# ai_orb-8.net
KiCad netlist of a schematic drawn in EAGLE
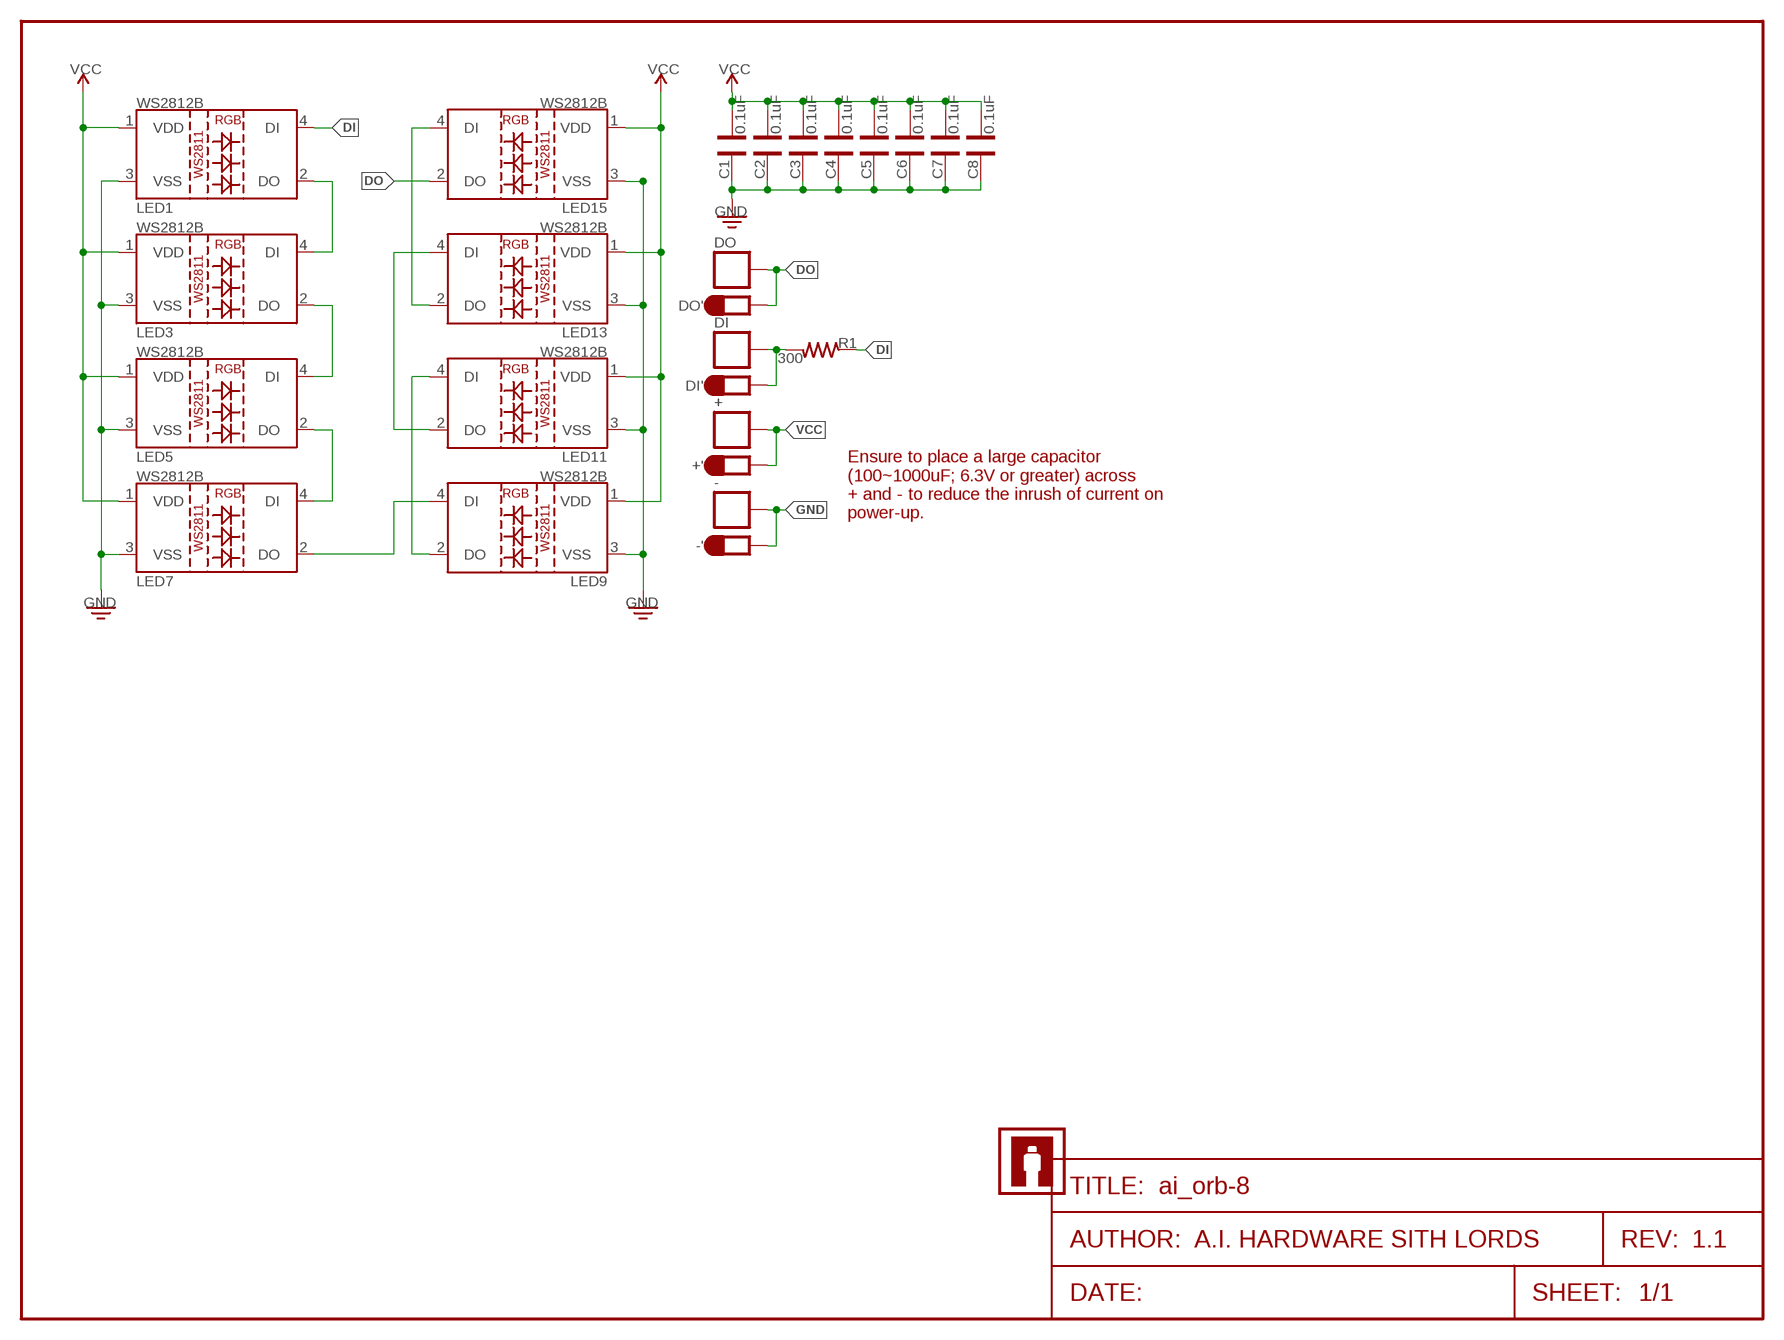
[diagram p0: schematic, sheet 1]

(export (version "E")
  (design (tool "Eeschema 10.0.6"))
  (components
    (comp (ref "+")
      (value "1X01-SM")
      (footprint "eagle-import:1X01-SM")
      (libsource (lib "eagle-import") (part "1X01-SM"))
    )
    (comp (ref "+'")
      (value "1X01-PETAL")
      (footprint "eagle-import:1X01-PETAL")
      (libsource (lib "eagle-import") (part "1X01-PETAL"))
    )
    (comp (ref "-")
      (value "1X01-SM")
      (footprint "eagle-import:1X01-SM")
      (libsource (lib "eagle-import") (part "1X01-SM"))
    )
    (comp (ref "-'")
      (value "1X01-PETAL")
      (footprint "eagle-import:1X01-PETAL")
      (libsource (lib "eagle-import") (part "1X01-PETAL"))
    )
    (comp (ref "C1")
      (value "0.1uF")
      (footprint "eagle-import:CAP-0402")
      (libsource (lib "eagle-import") (part "CAP0402"))
    )
    (comp (ref "C2")
      (value "0.1uF")
      (footprint "eagle-import:CAP-0402")
      (libsource (lib "eagle-import") (part "CAP0402"))
    )
    (comp (ref "C3")
      (value "0.1uF")
      (footprint "eagle-import:CAP-0402")
      (libsource (lib "eagle-import") (part "CAP0402"))
    )
    (comp (ref "C4")
      (value "0.1uF")
      (footprint "eagle-import:CAP-0402")
      (libsource (lib "eagle-import") (part "CAP0402"))
    )
    (comp (ref "C5")
      (value "0.1uF")
      (footprint "eagle-import:CAP-0402")
      (libsource (lib "eagle-import") (part "CAP0402"))
    )
    (comp (ref "C6")
      (value "0.1uF")
      (footprint "eagle-import:CAP-0402")
      (libsource (lib "eagle-import") (part "CAP0402"))
    )
    (comp (ref "C7")
      (value "0.1uF")
      (footprint "eagle-import:CAP-0402")
      (libsource (lib "eagle-import") (part "CAP0402"))
    )
    (comp (ref "C8")
      (value "0.1uF")
      (footprint "eagle-import:CAP-0402")
      (libsource (lib "eagle-import") (part "CAP0402"))
    )
    (comp (ref "DI")
      (value "1X01-SM")
      (footprint "eagle-import:1X01-SM")
      (libsource (lib "eagle-import") (part "1X01-SM"))
    )
    (comp (ref "DI'")
      (value "1X01-PETAL")
      (footprint "eagle-import:1X01-PETAL")
      (libsource (lib "eagle-import") (part "1X01-PETAL"))
    )
    (comp (ref "DO")
      (value "1X01-SM")
      (footprint "eagle-import:1X01-SM")
      (libsource (lib "eagle-import") (part "1X01-SM"))
    )
    (comp (ref "DO'")
      (value "1X01-PETAL")
      (footprint "eagle-import:1X01-PETAL")
      (libsource (lib "eagle-import") (part "1X01-PETAL"))
    )
    (comp (ref "LED1")
      (value "LED-WS2812B-SM")
      (footprint "eagle-import:LED-WS2812B-SM")
      (libsource (lib "eagle-import") (part "LED-WS2812B-SM"))
    )
    (comp (ref "LED3")
      (value "LED-WS2812B-SM")
      (footprint "eagle-import:LED-WS2812B-SM")
      (libsource (lib "eagle-import") (part "LED-WS2812B-SM"))
    )
    (comp (ref "LED5")
      (value "LED-WS2812B-SM")
      (footprint "eagle-import:LED-WS2812B-SM")
      (libsource (lib "eagle-import") (part "LED-WS2812B-SM"))
    )
    (comp (ref "LED7")
      (value "LED-WS2812B-SM")
      (footprint "eagle-import:LED-WS2812B-SM")
      (libsource (lib "eagle-import") (part "LED-WS2812B-SM"))
    )
    (comp (ref "LED9")
      (value "LED-WS2812B-SM")
      (footprint "eagle-import:LED-WS2812B-SM")
      (libsource (lib "eagle-import") (part "LED-WS2812B-SM"))
    )
    (comp (ref "LED11")
      (value "LED-WS2812B-SM")
      (footprint "eagle-import:LED-WS2812B-SM")
      (libsource (lib "eagle-import") (part "LED-WS2812B-SM"))
    )
    (comp (ref "LED13")
      (value "LED-WS2812B-SM")
      (footprint "eagle-import:LED-WS2812B-SM")
      (libsource (lib "eagle-import") (part "LED-WS2812B-SM"))
    )
    (comp (ref "LED15")
      (value "LED-WS2812B-SM")
      (footprint "eagle-import:LED-WS2812B-SM")
      (libsource (lib "eagle-import") (part "LED-WS2812B-SM"))
    )
    (comp (ref "LOGO")
      (value "AI-LOGOXS")
      (footprint "eagle-import:AI-LOGO-XS")
      (libsource (lib "eagle-import") (part "AI-LOGOXS"))
    )
    (comp (ref "LOGO1")
      (value "AI-LOGOXS")
      (footprint "eagle-import:AI-LOGO-XS")
      (libsource (lib "eagle-import") (part "AI-LOGOXS"))
    )
    (comp (ref "R1")
      (value "300")
      (footprint "eagle-import:RES-0402")
      (libsource (lib "eagle-import") (part "RES0402"))
    )
  )
  (nets
    (net (code "1") (name "DI") (class "Default")
      (node (ref "LED1") (pin "4") (pinfunction "DI_4") (pintype "bidirectional"))
      (node (ref "R1") (pin "1") (pinfunction "1_1") (pintype "passive"))
    )
    (net (code "2") (name "DO") (class "Default")
      (node (ref "DO") (pin "1") (pinfunction "1_1") (pintype "bidirectional"))
      (node (ref "DO'") (pin "1") (pinfunction "1_1") (pintype "bidirectional"))
      (node (ref "LED15") (pin "2") (pinfunction "DO_2") (pintype "bidirectional"))
    )
    (net (code "3") (name "GND") (class "Default")
      (node (ref "-") (pin "1") (pinfunction "1_1") (pintype "bidirectional"))
      (node (ref "-'") (pin "1") (pinfunction "1_1") (pintype "bidirectional"))
      (node (ref "C1") (pin "2") (pinfunction "2_2") (pintype "passive"))
      (node (ref "C2") (pin "2") (pinfunction "2_2") (pintype "passive"))
      (node (ref "C3") (pin "2") (pinfunction "2_2") (pintype "passive"))
      (node (ref "C4") (pin "2") (pinfunction "2_2") (pintype "passive"))
      (node (ref "C5") (pin "2") (pinfunction "2_2") (pintype "passive"))
      (node (ref "C6") (pin "2") (pinfunction "2_2") (pintype "passive"))
      (node (ref "C7") (pin "2") (pinfunction "2_2") (pintype "passive"))
      (node (ref "C8") (pin "2") (pinfunction "2_2") (pintype "passive"))
      (node (ref "LED1") (pin "3") (pinfunction "VSS_3") (pintype "bidirectional"))
      (node (ref "LED11") (pin "3") (pinfunction "VSS_3") (pintype "bidirectional"))
      (node (ref "LED13") (pin "3") (pinfunction "VSS_3") (pintype "bidirectional"))
      (node (ref "LED15") (pin "3") (pinfunction "VSS_3") (pintype "bidirectional"))
      (node (ref "LED3") (pin "3") (pinfunction "VSS_3") (pintype "bidirectional"))
      (node (ref "LED5") (pin "3") (pinfunction "VSS_3") (pintype "bidirectional"))
      (node (ref "LED7") (pin "3") (pinfunction "VSS_3") (pintype "bidirectional"))
      (node (ref "LED9") (pin "3") (pinfunction "VSS_3") (pintype "bidirectional"))
    )
    (net (code "4") (name "Net-(DI'-Pad1)") (class "Default")
      (node (ref "DI") (pin "1") (pinfunction "1_1") (pintype "bidirectional"))
      (node (ref "DI'") (pin "1") (pinfunction "1_1") (pintype "bidirectional"))
      (node (ref "R1") (pin "2") (pinfunction "2_2") (pintype "passive"))
    )
    (net (code "5") (name "Net-(LED1-DO)") (class "Default")
      (node (ref "LED1") (pin "2") (pinfunction "DO_2") (pintype "bidirectional"))
      (node (ref "LED3") (pin "4") (pinfunction "DI_4") (pintype "bidirectional"))
    )
    (net (code "6") (name "Net-(LED3-DO)") (class "Default")
      (node (ref "LED3") (pin "2") (pinfunction "DO_2") (pintype "bidirectional"))
      (node (ref "LED5") (pin "4") (pinfunction "DI_4") (pintype "bidirectional"))
    )
    (net (code "7") (name "Net-(LED5-DO)") (class "Default")
      (node (ref "LED5") (pin "2") (pinfunction "DO_2") (pintype "bidirectional"))
      (node (ref "LED7") (pin "4") (pinfunction "DI_4") (pintype "bidirectional"))
    )
    (net (code "8") (name "Net-(LED7-DO)") (class "Default")
      (node (ref "LED7") (pin "2") (pinfunction "DO_2") (pintype "bidirectional"))
      (node (ref "LED9") (pin "4") (pinfunction "DI_4") (pintype "bidirectional"))
    )
    (net (code "9") (name "Net-(LED11-DI)") (class "Default")
      (node (ref "LED11") (pin "4") (pinfunction "DI_4") (pintype "bidirectional"))
      (node (ref "LED9") (pin "2") (pinfunction "DO_2") (pintype "bidirectional"))
    )
    (net (code "10") (name "Net-(LED11-DO)") (class "Default")
      (node (ref "LED11") (pin "2") (pinfunction "DO_2") (pintype "bidirectional"))
      (node (ref "LED13") (pin "4") (pinfunction "DI_4") (pintype "bidirectional"))
    )
    (net (code "11") (name "Net-(LED13-DO)") (class "Default")
      (node (ref "LED13") (pin "2") (pinfunction "DO_2") (pintype "bidirectional"))
      (node (ref "LED15") (pin "4") (pinfunction "DI_4") (pintype "bidirectional"))
    )
    (net (code "12") (name "VCC") (class "Default")
      (node (ref "+") (pin "1") (pinfunction "1_1") (pintype "bidirectional"))
      (node (ref "+'") (pin "1") (pinfunction "1_1") (pintype "bidirectional"))
      (node (ref "C1") (pin "1") (pinfunction "1_1") (pintype "passive"))
      (node (ref "C2") (pin "1") (pinfunction "1_1") (pintype "passive"))
      (node (ref "C3") (pin "1") (pinfunction "1_1") (pintype "passive"))
      (node (ref "C4") (pin "1") (pinfunction "1_1") (pintype "passive"))
      (node (ref "C5") (pin "1") (pinfunction "1_1") (pintype "passive"))
      (node (ref "C6") (pin "1") (pinfunction "1_1") (pintype "passive"))
      (node (ref "C7") (pin "1") (pinfunction "1_1") (pintype "passive"))
      (node (ref "C8") (pin "1") (pinfunction "1_1") (pintype "passive"))
      (node (ref "LED1") (pin "1") (pinfunction "VDD_1") (pintype "bidirectional"))
      (node (ref "LED11") (pin "1") (pinfunction "VDD_1") (pintype "bidirectional"))
      (node (ref "LED13") (pin "1") (pinfunction "VDD_1") (pintype "bidirectional"))
      (node (ref "LED15") (pin "1") (pinfunction "VDD_1") (pintype "bidirectional"))
      (node (ref "LED3") (pin "1") (pinfunction "VDD_1") (pintype "bidirectional"))
      (node (ref "LED5") (pin "1") (pinfunction "VDD_1") (pintype "bidirectional"))
      (node (ref "LED7") (pin "1") (pinfunction "VDD_1") (pintype "bidirectional"))
      (node (ref "LED9") (pin "1") (pinfunction "VDD_1") (pintype "bidirectional"))
    )
  )
)
